# BW1092_LEFT_OV9282.net
KiCad netlist of a schematic drawn in Altium Designer
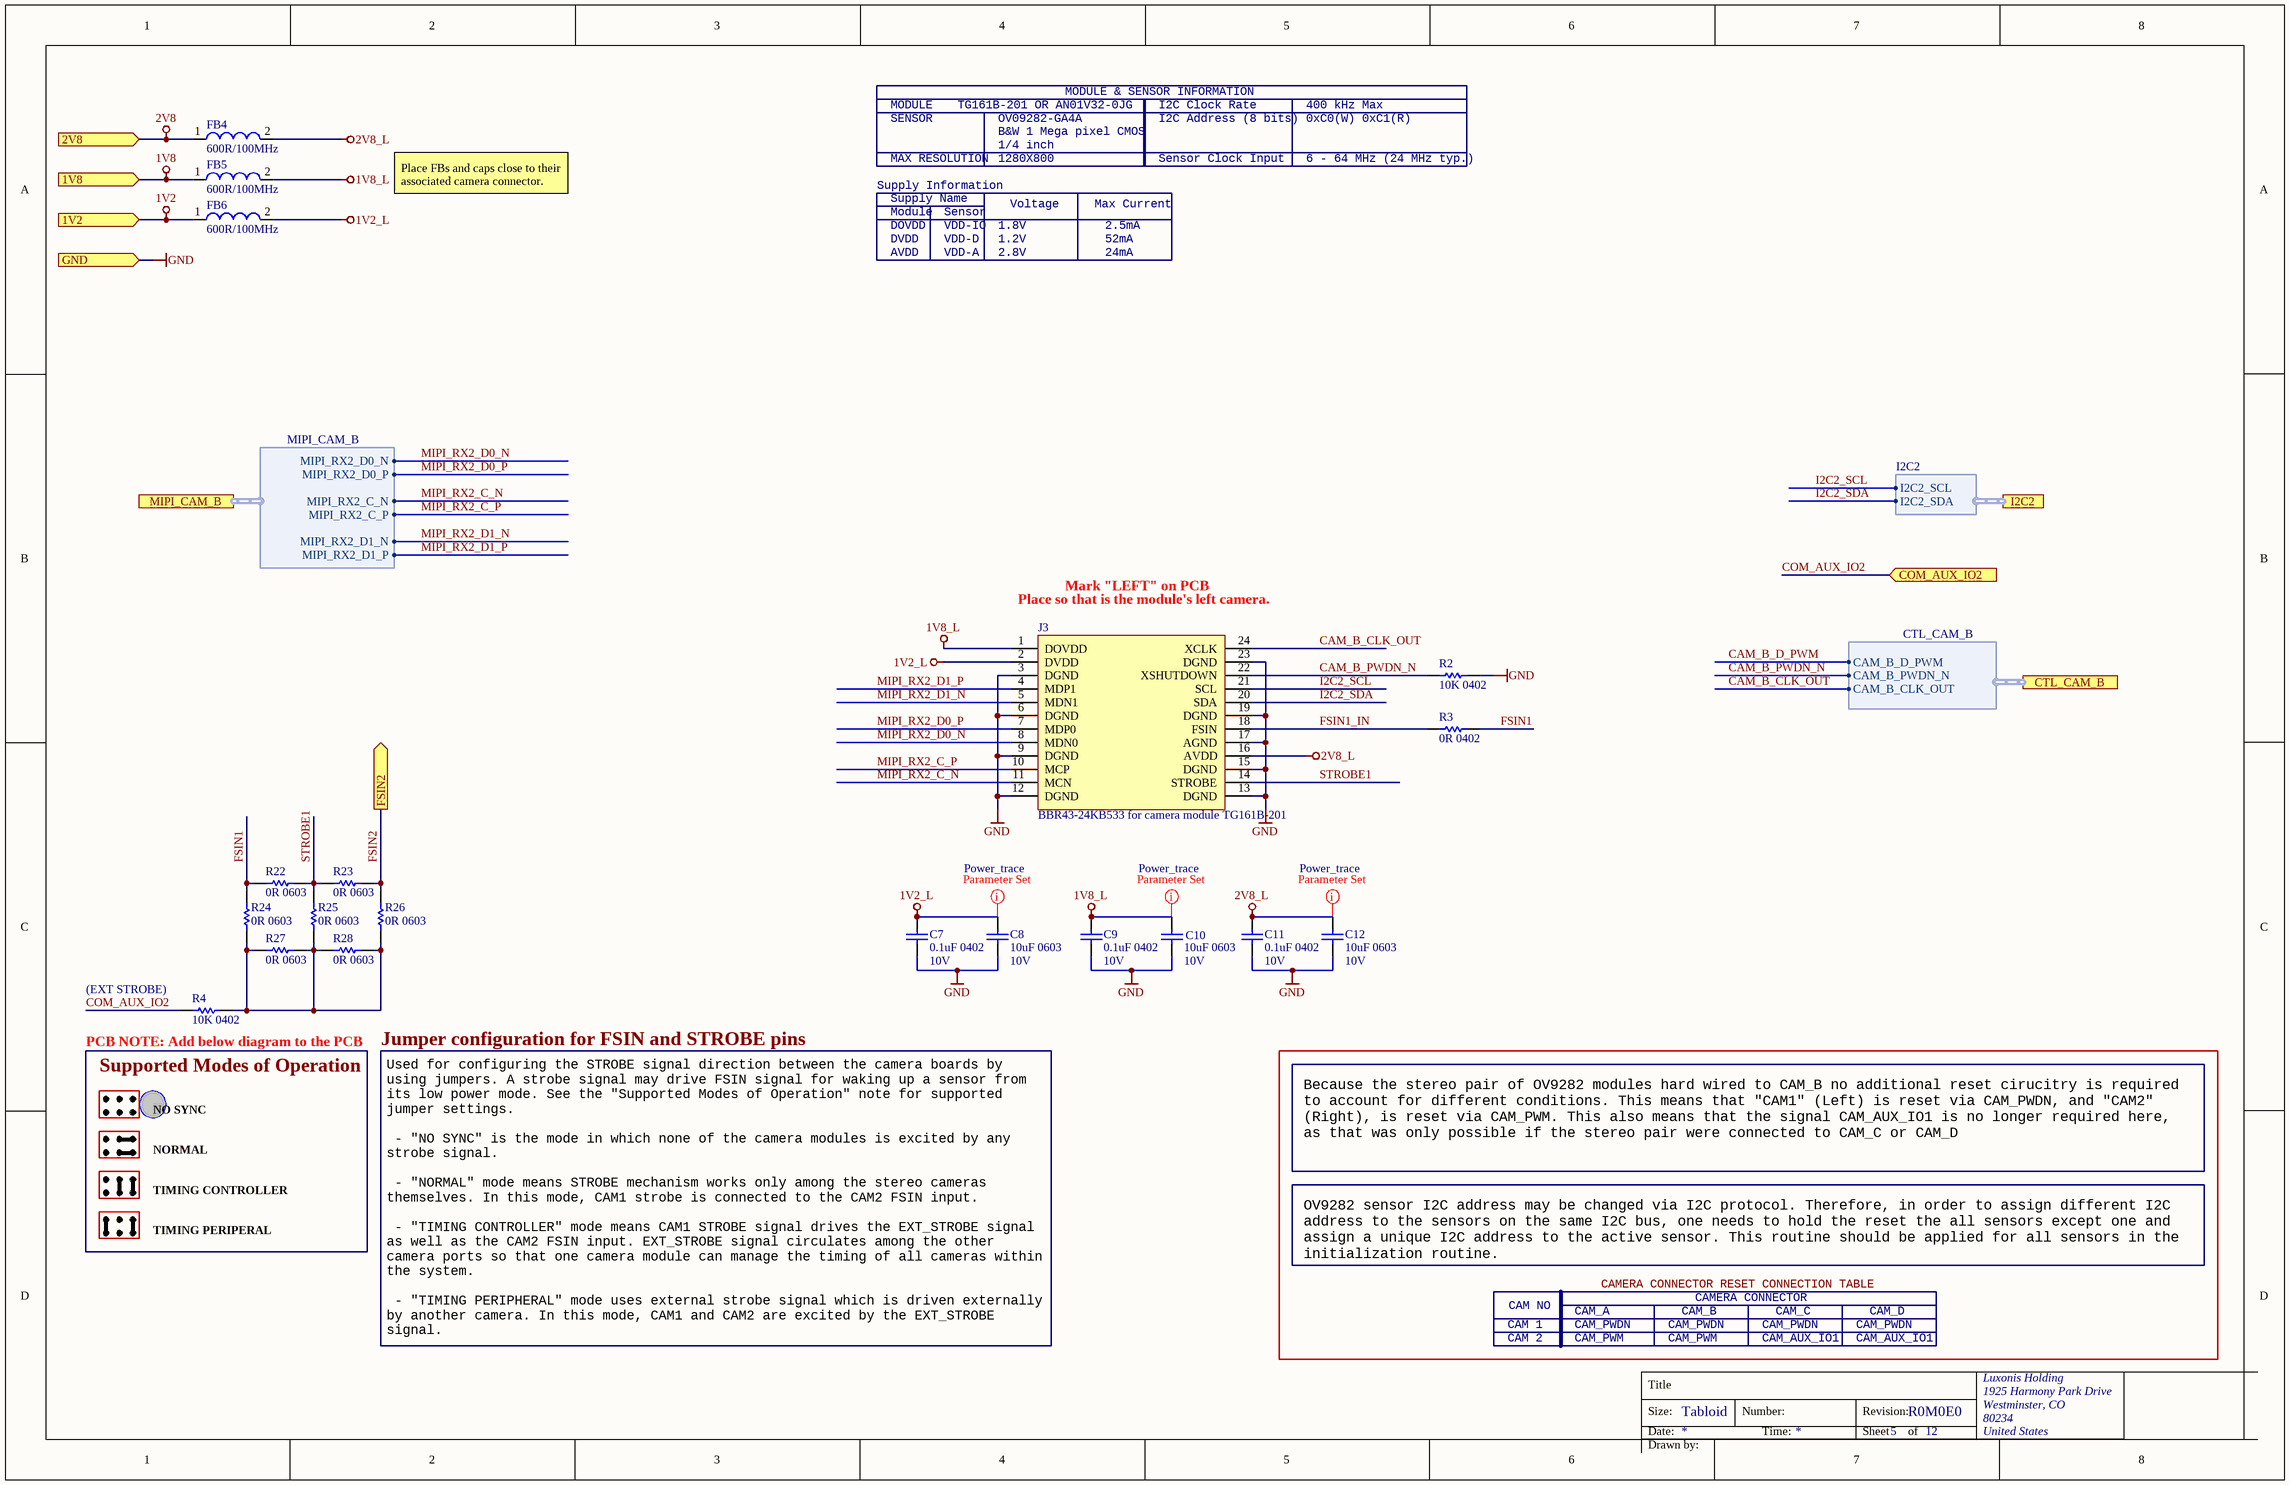
[diagram p0: BW1092_LEFT_OV9282.SchDoc]

(export (version "E")
  (design (tool "Eeschema 10.0.6"))
  (components
    (comp (ref "C7")
      (value "0.1uF 0402")
      (footprint "CAP_Altium_Vault_Generic:CAPC0402(1005)70_L")
      (description "CAP CER 0.1UF 10V X7R 0402 5%")
      (fields (field (name "TOLERANCE") "5%") (field (name "VOLTAGE RATING") "10V"))
      (libsource (lib "LuxonisMaster") (part "GRM155R71A104JA01D"))
    )
    (comp (ref "C8")
      (value "10uF 0603")
      (footprint "CAP_Altium_Vault_Generic:CAPC0603(1608)100_L")
      (description "CAP CER 10UF 10V X5R 0603 20%")
      (fields (field (name "TOLERANCE") "20%") (field (name "VOLTAGE RATING") "10V"))
      (libsource (lib "LuxonisMaster") (part "GRM188R61A106ME69D"))
    )
    (comp (ref "C9")
      (value "0.1uF 0402")
      (footprint "CAP_Altium_Vault_Generic:CAPC0402(1005)70_L")
      (description "CAP CER 0.1UF 10V X7R 0402 5%")
      (fields (field (name "TOLERANCE") "5%") (field (name "VOLTAGE RATING") "10V"))
      (libsource (lib "LuxonisMaster") (part "GRM155R71A104JA01D"))
    )
    (comp (ref "C10")
      (value "10uF 0603")
      (footprint "CAP_Altium_Vault_Generic:CAPC0603(1608)100_L")
      (description "CAP CER 10UF 10V X5R 0603 20%")
      (fields (field (name "TOLERANCE") "20%") (field (name "VOLTAGE RATING") "10V"))
      (libsource (lib "LuxonisMaster") (part "GRM188R61A106ME69D"))
    )
    (comp (ref "C11")
      (value "0.1uF 0402")
      (footprint "CAP_Altium_Vault_Generic:CAPC0402(1005)70_L")
      (description "CAP CER 0.1UF 10V X7R 0402 5%")
      (fields (field (name "TOLERANCE") "5%") (field (name "VOLTAGE RATING") "10V"))
      (libsource (lib "LuxonisMaster") (part "GRM155R71A104JA01D"))
    )
    (comp (ref "C12")
      (value "10uF 0603")
      (footprint "CAP_Altium_Vault_Generic:CAPC0603(1608)100_L")
      (description "CAP CER 10UF 10V X5R 0603 20%")
      (fields (field (name "TOLERANCE") "20%") (field (name "VOLTAGE RATING") "10V"))
      (libsource (lib "LuxonisMaster") (part "GRM188R61A106ME69D"))
    )
    (comp (ref "FB4")
      (value "600R/100MHz")
      (footprint "LuxonisMaster:2508056017Y2")
      (description "FERRITE BEAD, 0.1OHM, 2A, 0805, 600R/100MHz")
      (fields (field (name "TOLERANCE") "25%"))
      (libsource (lib "LuxonisMaster") (part "2508056017Y2"))
    )
    (comp (ref "FB5")
      (value "600R/100MHz")
      (footprint "LuxonisMaster:2508056017Y2")
      (description "FERRITE BEAD, 0.1OHM, 2A, 0805, 600R/100MHz")
      (fields (field (name "TOLERANCE") "25%"))
      (libsource (lib "LuxonisMaster") (part "2508056017Y2"))
    )
    (comp (ref "FB6")
      (value "600R/100MHz")
      (footprint "LuxonisMaster:2508056017Y2")
      (description "FERRITE BEAD, 0.1OHM, 2A, 0805, 600R/100MHz")
      (fields (field (name "TOLERANCE") "25%"))
      (libsource (lib "LuxonisMaster") (part "2508056017Y2"))
    )
    (comp (ref "J3")
      (value "BBR43-24KB533 for camera module TG161B-201")
      (footprint "LuxonisMaster:TG161B-201_HD")
      (description "CONN 24 way, 2 row board to board connector SMD")
      (libsource (lib "LuxonisMaster") (part "TG161B-201_Connector"))
    )
    (comp (ref "R2")
      (value "10K 0402")
      (footprint "RES_Altium_Vault_Generic:RESC0402(1005)_L")
      (fields (field (name "TOLERANCE") "1%"))
      (libsource (lib "LuxonisMaster") (part "RC0402FR-1310KL"))
    )
    (comp (ref "R3")
      (value "0R 0402")
      (footprint "RES_Altium_Vault_Generic:RESC0402(1005)_L")
      (description "RES SMD 0 OHM JUMPER 1/16W 0402")
      (fields (field (name "TOLERANCE") "5%"))
      (libsource (lib "LuxonisMaster") (part "CRCW04020000Z0ED"))
    )
    (comp (ref "R4")
      (value "10K 0402")
      (footprint "RES_Altium_Vault_Generic:RESC0402(1005)_L")
      (fields (field (name "TOLERANCE") "1%"))
      (libsource (lib "LuxonisMaster") (part "RC0402FR-1310KL"))
    )
    (comp (ref "R22")
      (value "0R 0603")
      (footprint "RES_Altium_Vault_Generic:RESC0603(1608)_N")
      (fields (field (name "TOLERANCE") "5%"))
      (libsource (lib "LuxonisMaster") (part "CRCW06030000Z0EA"))
    )
    (comp (ref "R23")
      (value "0R 0603")
      (footprint "RES_Altium_Vault_Generic:RESC0603(1608)_N")
      (fields (field (name "TOLERANCE") "5%"))
      (libsource (lib "LuxonisMaster") (part "CRCW06030000Z0EA"))
    )
    (comp (ref "R24")
      (value "0R 0603")
      (footprint "RES_Altium_Vault_Generic:RESC0603(1608)_N")
      (fields (field (name "TOLERANCE") "5%"))
      (libsource (lib "LuxonisMaster") (part "CRCW06030000Z0EA"))
    )
    (comp (ref "R25")
      (value "0R 0603")
      (footprint "RES_Altium_Vault_Generic:RESC0603(1608)_N")
      (fields (field (name "TOLERANCE") "5%"))
      (libsource (lib "LuxonisMaster") (part "CRCW06030000Z0EA"))
    )
    (comp (ref "R26")
      (value "0R 0603")
      (footprint "RES_Altium_Vault_Generic:RESC0603(1608)_N")
      (fields (field (name "TOLERANCE") "5%"))
      (libsource (lib "LuxonisMaster") (part "CRCW06030000Z0EA"))
    )
    (comp (ref "R27")
      (value "0R 0603")
      (footprint "RES_Altium_Vault_Generic:RESC0603(1608)_N")
      (fields (field (name "TOLERANCE") "5%"))
      (libsource (lib "LuxonisMaster") (part "CRCW06030000Z0EA"))
    )
    (comp (ref "R28")
      (value "0R 0603")
      (footprint "RES_Altium_Vault_Generic:RESC0603(1608)_N")
      (fields (field (name "TOLERANCE") "5%"))
      (libsource (lib "LuxonisMaster") (part "CRCW06030000Z0EA"))
    )
  )
  (nets
    (net (code "4") (name "/CAM_B_CLK_OUT") (class "Default")
      (node (ref "J3") (pin "24") (pinfunction "XCLK_24") (pintype "passive"))
    )
    (net (code "6") (name "/CAM_B_PWDN_N") (class "Default")
      (node (ref "J3") (pin "22") (pinfunction "XSHUTDOWN_22") (pintype "passive"))
      (node (ref "R2") (pin "1") (pinfunction "1_1") (pintype "passive"))
    )
    (net (code "7") (name "/COM_AUX_IO2") (class "Default")
      (node (ref "R4") (pin "1") (pinfunction "1_1") (pintype "passive"))
    )
    (net (code "8") (name "/FSIN1") (class "Default")
      (node (ref "R22") (pin "1") (pinfunction "1_1") (pintype "passive"))
      (node (ref "R24") (pin "2") (pinfunction "2_2") (pintype "passive"))
      (node (ref "R3") (pin "2") (pinfunction "2_2") (pintype "passive"))
    )
    (net (code "9") (name "/FSIN1_IN") (class "Default")
      (node (ref "J3") (pin "18") (pinfunction "FSIN_18") (pintype "passive"))
      (node (ref "R3") (pin "1") (pinfunction "1_1") (pintype "passive"))
    )
    (net (code "10") (name "/FSIN2") (class "Default")
      (node (ref "R23") (pin "2") (pinfunction "2_2") (pintype "passive"))
      (node (ref "R26") (pin "2") (pinfunction "2_2") (pintype "passive"))
    )
    (net (code "11") (name "/I2C2_SCL") (class "Default")
      (node (ref "J3") (pin "21") (pinfunction "SCL_21") (pintype "passive"))
    )
    (net (code "12") (name "/I2C2_SDA") (class "Default")
      (node (ref "J3") (pin "20") (pinfunction "SDA_20") (pintype "passive"))
    )
    (net (code "13") (name "/MIPI_RX2_C_N") (class "Default")
      (node (ref "J3") (pin "11") (pinfunction "MCN_11") (pintype "passive"))
    )
    (net (code "14") (name "/MIPI_RX2_C_P") (class "Default")
      (node (ref "J3") (pin "10") (pinfunction "MCP_10") (pintype "passive"))
    )
    (net (code "15") (name "/MIPI_RX2_D0_N") (class "Default")
      (node (ref "J3") (pin "8") (pinfunction "MDN0_8") (pintype "passive"))
    )
    (net (code "16") (name "/MIPI_RX2_D0_P") (class "Default")
      (node (ref "J3") (pin "7") (pinfunction "MDP0_7") (pintype "passive"))
    )
    (net (code "17") (name "/MIPI_RX2_D1_N") (class "Default")
      (node (ref "J3") (pin "5") (pinfunction "MDN1_5") (pintype "passive"))
    )
    (net (code "18") (name "/MIPI_RX2_D1_P") (class "Default")
      (node (ref "J3") (pin "4") (pinfunction "MDP1_4") (pintype "passive"))
    )
    (net (code "19") (name "/STROBE1") (class "Default")
      (node (ref "J3") (pin "14") (pinfunction "STROBE_14") (pintype "passive"))
      (node (ref "R22") (pin "2") (pinfunction "2_2") (pintype "passive"))
      (node (ref "R23") (pin "1") (pinfunction "1_1") (pintype "passive"))
      (node (ref "R25") (pin "2") (pinfunction "2_2") (pintype "passive"))
    )
    (net (code "23") (name "1V2") (class "Default")
      (node (ref "FB6") (pin "1") (pinfunction "1_1") (pintype "passive"))
    )
    (net (code "24") (name "1V2_L") (class "Default")
      (node (ref "C7") (pin "2") (pinfunction "2_2") (pintype "passive"))
      (node (ref "C8") (pin "2") (pinfunction "2_2") (pintype "passive"))
      (node (ref "FB6") (pin "2") (pinfunction "2_2") (pintype "passive"))
      (node (ref "J3") (pin "2") (pinfunction "DVDD_2") (pintype "passive"))
    )
    (net (code "25") (name "1V8") (class "Default")
      (node (ref "FB5") (pin "1") (pinfunction "1_1") (pintype "passive"))
    )
    (net (code "26") (name "1V8_L") (class "Default")
      (node (ref "C10") (pin "2") (pinfunction "2_2") (pintype "passive"))
      (node (ref "C9") (pin "2") (pinfunction "2_2") (pintype "passive"))
      (node (ref "FB5") (pin "2") (pinfunction "2_2") (pintype "passive"))
      (node (ref "J3") (pin "1") (pinfunction "DOVDD_1") (pintype "passive"))
    )
    (net (code "27") (name "2V8") (class "Default")
      (node (ref "FB4") (pin "1") (pinfunction "1_1") (pintype "passive"))
    )
    (net (code "28") (name "2V8_L") (class "Default")
      (node (ref "C11") (pin "2") (pinfunction "2_2") (pintype "passive"))
      (node (ref "C12") (pin "2") (pinfunction "2_2") (pintype "passive"))
      (node (ref "FB4") (pin "2") (pinfunction "2_2") (pintype "passive"))
      (node (ref "J3") (pin "16") (pinfunction "AVDD_16") (pintype "passive"))
    )
    (net (code "29") (name "GND") (class "Default")
      (node (ref "C10") (pin "1") (pinfunction "1_1") (pintype "passive"))
      (node (ref "C11") (pin "1") (pinfunction "1_1") (pintype "passive"))
      (node (ref "C12") (pin "1") (pinfunction "1_1") (pintype "passive"))
      (node (ref "C7") (pin "1") (pinfunction "1_1") (pintype "passive"))
      (node (ref "C8") (pin "1") (pinfunction "1_1") (pintype "passive"))
      (node (ref "C9") (pin "1") (pinfunction "1_1") (pintype "passive"))
      (node (ref "J3") (pin "12") (pinfunction "DGND_12") (pintype "passive"))
      (node (ref "J3") (pin "13") (pinfunction "DGND_13") (pintype "passive"))
      (node (ref "J3") (pin "15") (pinfunction "DGND_15") (pintype "passive"))
      (node (ref "J3") (pin "17") (pinfunction "AGND_17") (pintype "passive"))
      (node (ref "J3") (pin "19") (pinfunction "DGND_19") (pintype "passive"))
      (node (ref "J3") (pin "23") (pinfunction "DGND_23") (pintype "passive"))
      (node (ref "J3") (pin "3") (pinfunction "DGND_3") (pintype "passive"))
      (node (ref "J3") (pin "6") (pinfunction "DGND_6") (pintype "passive"))
      (node (ref "J3") (pin "9") (pinfunction "DGND_9") (pintype "passive"))
      (node (ref "R2") (pin "2") (pinfunction "2_2") (pintype "passive"))
    )
    (net (code "30") (name "Net-(R24-Pad1)") (class "Default")
      (node (ref "R24") (pin "1") (pinfunction "1_1") (pintype "passive"))
      (node (ref "R25") (pin "1") (pinfunction "1_1") (pintype "passive"))
      (node (ref "R26") (pin "1") (pinfunction "1_1") (pintype "passive"))
      (node (ref "R27") (pin "1") (pinfunction "1_1") (pintype "passive"))
      (node (ref "R27") (pin "2") (pinfunction "2_2") (pintype "passive"))
      (node (ref "R28") (pin "1") (pinfunction "1_1") (pintype "passive"))
      (node (ref "R28") (pin "2") (pinfunction "2_2") (pintype "passive"))
      (node (ref "R4") (pin "2") (pinfunction "2_2") (pintype "passive"))
    )
  )
)
